# Sheet2.net
KiCad netlist of a schematic drawn in Altium Designer
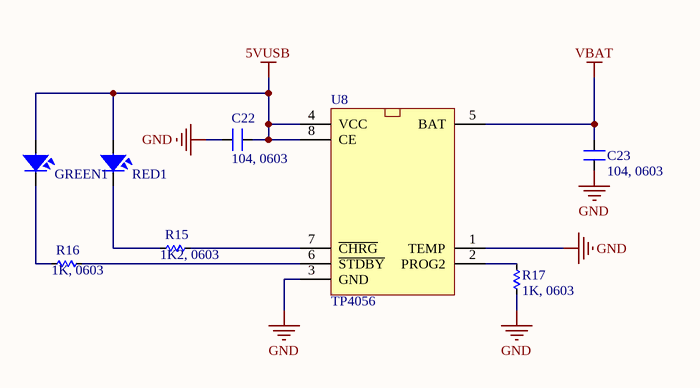
[diagram p0: Sheet2.SchDoc]

(export (version "E")
  (design (tool "Eeschema 10.0.6"))
  (components
    (comp (ref "C22")
      (value "104, 0603")
      (footprint "SM-0603")
      (description "Cap SMD")
      (libsource (lib "KhanhBK_Library_4") (part "CM"))
    )
    (comp (ref "C23")
      (value "104, 0603")
      (footprint "SM-0603")
      (description "Cap SMD")
      (libsource (lib "KhanhBK_Library_4") (part "CM"))
    )
    (comp (ref "GREEN1")
      (value "LED")
      (footprint "LED-0805-Blue")
      (libsource (lib "KhanhBK_SCH_Library_1") (part "LED SMD"))
    )
    (comp (ref "R15")
      (value "1K2, 0603")
      (footprint "RES-SMD-0603")
      (description "Resistor")
      (fields
        (field (name "MANUFACTURER") "Generic Components")
        (field (name "PUBLISHER") "Altium Hobart Technology Centre")
      )
      (libsource (lib "KhanhBK_SCH_Library_1") (part "Res-SMD"))
    )
    (comp (ref "R16")
      (value "1K, 0603")
      (footprint "RES-SMD-0603")
      (description "Resistor")
      (fields
        (field (name "MANUFACTURER") "Generic Components")
        (field (name "PUBLISHER") "Altium Hobart Technology Centre")
      )
      (libsource (lib "KhanhBK_SCH_Library_1") (part "Res-SMD"))
    )
    (comp (ref "R17")
      (value "1K, 0603")
      (footprint "RES-SMD-0603")
      (description "Resistor")
      (fields
        (field (name "MANUFACTURER") "Generic Components")
        (field (name "PUBLISHER") "Altium Hobart Technology Centre")
      )
      (libsource (lib "KhanhBK_SCH_Library_1") (part "Res-SMD"))
    )
    (comp (ref "RED1")
      (value "LED")
      (footprint "LED-0805-Blue")
      (libsource (lib "KhanhBK_SCH_Library_1") (part "LED SMD"))
    )
    (comp (ref "U8")
      (value "TP4056")
      (footprint "MinhTien_PcbLib:SOP8_L")
      (description "1A Standalone Linear Li-lon Battery Charger with Thermal   Regulation")
      (libsource (lib "KhanhBK_SCH_Lib_5") (part "TP4056"))
    )
  )
  (nets
    (net (code "1") (name "5VUSB") (class "Default")
      (node (ref "C22") (pin "1") (pinfunction "1_1") (pintype "passive"))
      (node (ref "GREEN1") (pin "1") (pinfunction "1_1") (pintype "passive"))
      (node (ref "RED1") (pin "1") (pinfunction "1_1") (pintype "passive"))
      (node (ref "U8") (pin "4") (pinfunction "VCC_4") (pintype "passive"))
      (node (ref "U8") (pin "8") (pinfunction "CE_8") (pintype "passive"))
    )
    (net (code "2") (name "GND") (class "Default")
      (node (ref "C22") (pin "2") (pinfunction "2_2") (pintype "passive"))
      (node (ref "C23") (pin "2") (pinfunction "2_2") (pintype "passive"))
      (node (ref "R17") (pin "2") (pinfunction "2_2") (pintype "passive"))
      (node (ref "U8") (pin "1") (pinfunction "TEMP_1") (pintype "passive"))
      (node (ref "U8") (pin "3") (pinfunction "GND_3") (pintype "passive"))
    )
    (net (code "3") (name "Net-(GREEN1-Pad2)") (class "Default")
      (node (ref "GREEN1") (pin "2") (pinfunction "2_2") (pintype "passive"))
      (node (ref "R16") (pin "2") (pinfunction "2_2") (pintype "passive"))
    )
    (net (code "4") (name "Net-(R15-Pad2)") (class "Default")
      (node (ref "R15") (pin "2") (pinfunction "2_2") (pintype "passive"))
      (node (ref "RED1") (pin "2") (pinfunction "2_2") (pintype "passive"))
    )
    (net (code "5") (name "Net-(U8-PROG2)") (class "Default")
      (node (ref "R17") (pin "1") (pinfunction "1_1") (pintype "passive"))
      (node (ref "U8") (pin "2") (pinfunction "PROG2_2") (pintype "passive"))
    )
    (net (code "6") (name "Net-(U8-~{CHRG})") (class "Default")
      (node (ref "R15") (pin "1") (pinfunction "1_1") (pintype "passive"))
      (node (ref "U8") (pin "7") (pinfunction "~{CHRG}_7") (pintype "passive"))
    )
    (net (code "7") (name "Net-(U8-~{STDBY})") (class "Default")
      (node (ref "R16") (pin "1") (pinfunction "1_1") (pintype "passive"))
      (node (ref "U8") (pin "6") (pinfunction "~{STDBY}_6") (pintype "passive"))
    )
    (net (code "8") (name "VBAT") (class "Default")
      (node (ref "C23") (pin "1") (pinfunction "1_1") (pintype "passive"))
      (node (ref "U8") (pin "5") (pinfunction "BAT_5") (pintype "passive"))
    )
  )
)
